# Power.net
KiCad netlist of a schematic drawn in Altium Designer
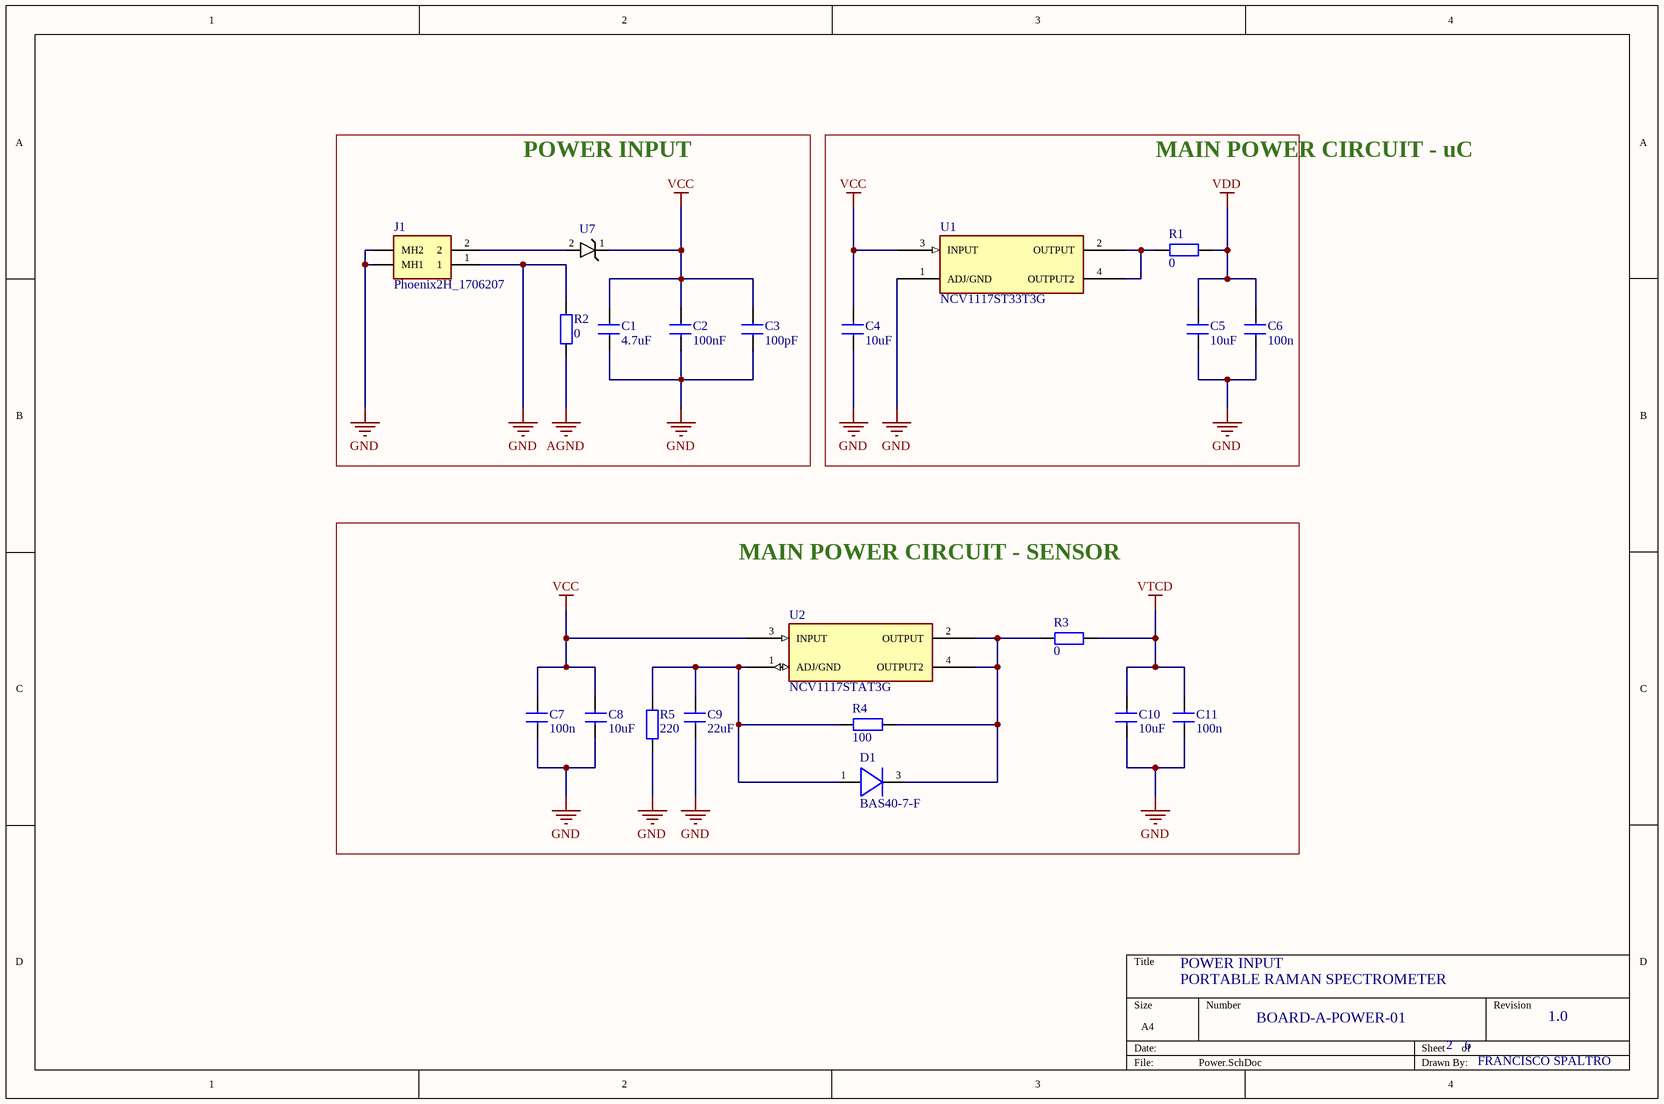
[diagram p0: Power.SchDoc]

(export (version "E")
  (design (tool "Eeschema 10.0.6"))
  (components
    (comp (ref "C1")
      (value "4.7uF")
      (footprint "RES_0805")
      (description "Generic Capacitor")
      (libsource (lib "Components") (part "CAP_0805"))
    )
    (comp (ref "C2")
      (value "100nF")
      (footprint "RES_0805")
      (description "Generic Capacitor")
      (libsource (lib "Components") (part "CAP_0805"))
    )
    (comp (ref "C3")
      (value "100pF")
      (footprint "RES_0805")
      (description "Generic Capacitor")
      (libsource (lib "Components") (part "CAP_0805"))
    )
    (comp (ref "C4")
      (value "10uF")
      (footprint "RES_0805")
      (description "Generic Capacitor")
      (libsource (lib "Components") (part "CAP_0805"))
    )
    (comp (ref "C5")
      (value "10uF")
      (footprint "RES_0805")
      (description "Generic Capacitor")
      (libsource (lib "Components") (part "CAP_0805"))
    )
    (comp (ref "C6")
      (value "100n")
      (footprint "RES_0805")
      (description "Generic Capacitor")
      (libsource (lib "") (part "CAP_0805_1"))
    )
    (comp (ref "C7")
      (value "100n")
      (footprint "RES_0805")
      (description "Generic Capacitor")
      (libsource (lib "") (part "CAP_0805_1"))
    )
    (comp (ref "C8")
      (value "10uF")
      (footprint "RES_0805")
      (description "Generic Capacitor")
      (libsource (lib "Components") (part "CAP_0805"))
    )
    (comp (ref "C9")
      (value "22uF")
      (footprint "RES_0805")
      (description "Generic Capacitor")
      (libsource (lib "Components") (part "CAP_0805"))
    )
    (comp (ref "C10")
      (value "10uF")
      (footprint "RES_0805")
      (description "Generic Capacitor")
      (libsource (lib "Components") (part "CAP_0805"))
    )
    (comp (ref "C11")
      (value "100n")
      (footprint "RES_0805")
      (description "Generic Capacitor")
      (libsource (lib "") (part "CAP_0805_1"))
    )
    (comp (ref "D1")
      (value "BAS40-7-F")
      (footprint "SOT-23_DIO-M")
      (description "Description")
      (fields (field (name "COPYRIGHT") "Copyright (C) 2025 Ultra Librarian. All rights reserved."))
      (libsource (lib "Components") (part "DIODE-BAS40-7-F"))
    )
    (comp (ref "J1")
      (value "Phoenix2H_1706207")
      (footprint "PHOENIX_1706207")
      (fields (field (name "MP") "1706207"))
      (libsource (lib "Components") (part "Phoenix2H_1706207"))
    )
    (comp (ref "R1")
      (value "0")
      (footprint "RES_0805")
      (description "Generic Capacitor")
      (libsource (lib "Components") (part "RES_0805"))
    )
    (comp (ref "R2")
      (value "0")
      (footprint "RES_0805")
      (description "Generic Capacitor")
      (libsource (lib "Components") (part "RES_0805"))
    )
    (comp (ref "R3")
      (value "0")
      (footprint "RES_0805")
      (description "Generic Capacitor")
      (libsource (lib "Components") (part "RES_0805"))
    )
    (comp (ref "R4")
      (value "100")
      (footprint "RES_0805")
      (description "Generic Capacitor")
      (libsource (lib "Components") (part "RES_0805"))
    )
    (comp (ref "R5")
      (value "220")
      (footprint "RES_0805")
      (description "Generic Capacitor")
      (libsource (lib "Components") (part "RES_0805"))
    )
    (comp (ref "U1")
      (value "NCV1117ST33T3G")
      (footprint "SOT230P700X180-4N")
      (description "Linear Voltage Regulator IC Positive Fixed 1 Output 1A SOT-223")
      (fields (field (name "MF") "ON Semiconductor"))
      (libsource (lib "CI") (part "REG3_3-NCV1117ST33T3G"))
    )
    (comp (ref "U2")
      (value "NCV1117STAT3G")
      (footprint "SOT223-3_ONS-M")
      (description "Description")
      (fields (field (name "COPYRIGHT") "Copyright (C) 2025 Ultra Librarian. All rights reserved."))
      (libsource (lib "Components") (part "NCV1117STAT3G"))
    )
    (comp (ref "U7")
      (value "MBRA340T3G")
      (footprint "SMA_ONS")
      (description "Description")
      (fields (field (name "COPYRIGHT") "Copyright (C) 2025 Ultra Librarian. All rights reserved."))
      (libsource (lib "Components") (part "MBRA340T3G"))
    )
  )
  (nets
    (net (code "1") (name "AGND") (class "Default")
      (node (ref "R2") (pin "1") (pinfunction "1_1") (pintype "passive"))
    )
    (net (code "2") (name "GND") (class "Default")
      (node (ref "C1") (pin "1") (pinfunction "1_1") (pintype "passive"))
      (node (ref "C10") (pin "1") (pinfunction "1_1") (pintype "passive"))
      (node (ref "C11") (pin "1") (pinfunction "1_1") (pintype "passive"))
      (node (ref "C2") (pin "1") (pinfunction "1_1") (pintype "passive"))
      (node (ref "C3") (pin "1") (pinfunction "1_1") (pintype "passive"))
      (node (ref "C4") (pin "1") (pinfunction "1_1") (pintype "passive"))
      (node (ref "C5") (pin "1") (pinfunction "1_1") (pintype "passive"))
      (node (ref "C6") (pin "1") (pinfunction "1_1") (pintype "passive"))
      (node (ref "C7") (pin "1") (pinfunction "1_1") (pintype "passive"))
      (node (ref "C8") (pin "1") (pinfunction "1_1") (pintype "passive"))
      (node (ref "C9") (pin "1") (pinfunction "1_1") (pintype "passive"))
      (node (ref "J1") (pin "1") (pinfunction "1_1") (pintype "passive"))
      (node (ref "J1") (pin "MH1") (pinfunction "MH1_MH1") (pintype "passive"))
      (node (ref "J1") (pin "MH2") (pinfunction "MH2_MH2") (pintype "passive"))
      (node (ref "R2") (pin "2") (pinfunction "2_2") (pintype "passive"))
      (node (ref "R5") (pin "1") (pinfunction "1_1") (pintype "passive"))
      (node (ref "U1") (pin "1") (pinfunction "ADJ/GND_1") (pintype "power_in"))
    )
    (net (code "3") (name "Net-(D1-A)") (class "Default")
      (node (ref "C9") (pin "2") (pinfunction "2_2") (pintype "passive"))
      (node (ref "D1") (pin "1") (pinfunction "A_1") (pintype "passive"))
      (node (ref "R4") (pin "2") (pinfunction "2_2") (pintype "passive"))
      (node (ref "R5") (pin "2") (pinfunction "2_2") (pintype "passive"))
      (node (ref "U2") (pin "1") (pinfunction "ADJ/GND_1") (pintype "bidirectional"))
    )
    (net (code "4") (name "Net-(D1-C)") (class "Default")
      (node (ref "D1") (pin "3") (pinfunction "C_3") (pintype "passive"))
      (node (ref "R3") (pin "1") (pinfunction "1_1") (pintype "passive"))
      (node (ref "R4") (pin "1") (pinfunction "1_1") (pintype "passive"))
      (node (ref "U2") (pin "2") (pinfunction "OUTPUT_2") (pintype "passive"))
      (node (ref "U2") (pin "4") (pinfunction "OUTPUT2_4") (pintype "passive"))
    )
    (net (code "5") (name "Net-(U1-OUTPUT)") (class "Default")
      (node (ref "R1") (pin "1") (pinfunction "1_1") (pintype "passive"))
      (node (ref "U1") (pin "2") (pinfunction "OUTPUT_2") (pintype "passive"))
      (node (ref "U1") (pin "4") (pinfunction "OUTPUT2_4") (pintype "passive"))
    )
    (net (code "6") (name "Net-(U7-ANODE)") (class "Default")
      (node (ref "J1") (pin "2") (pinfunction "2_2") (pintype "power_in"))
      (node (ref "U7") (pin "2") (pinfunction "ANODE_2") (pintype "passive"))
    )
    (net (code "7") (name "VCC") (class "Default")
      (node (ref "C1") (pin "2") (pinfunction "2_2") (pintype "passive"))
      (node (ref "C2") (pin "2") (pinfunction "2_2") (pintype "passive"))
      (node (ref "C3") (pin "2") (pinfunction "2_2") (pintype "passive"))
      (node (ref "C4") (pin "2") (pinfunction "2_2") (pintype "passive"))
      (node (ref "C7") (pin "2") (pinfunction "2_2") (pintype "passive"))
      (node (ref "C8") (pin "2") (pinfunction "2_2") (pintype "passive"))
      (node (ref "U1") (pin "3") (pinfunction "INPUT_3") (pintype "input"))
      (node (ref "U2") (pin "3") (pinfunction "INPUT_3") (pintype "input"))
      (node (ref "U7") (pin "1") (pinfunction "CATHODE_1") (pintype "passive"))
    )
    (net (code "8") (name "VDD") (class "Default")
      (node (ref "C5") (pin "2") (pinfunction "2_2") (pintype "passive"))
      (node (ref "C6") (pin "2") (pinfunction "2_2") (pintype "passive"))
      (node (ref "R1") (pin "2") (pinfunction "2_2") (pintype "passive"))
    )
    (net (code "9") (name "VTCD") (class "Default")
      (node (ref "C10") (pin "2") (pinfunction "2_2") (pintype "passive"))
      (node (ref "C11") (pin "2") (pinfunction "2_2") (pintype "passive"))
      (node (ref "R3") (pin "2") (pinfunction "2_2") (pintype "passive"))
    )
  )
)
